# Output_block.net
KiCad netlist of a schematic drawn in Altium Designer
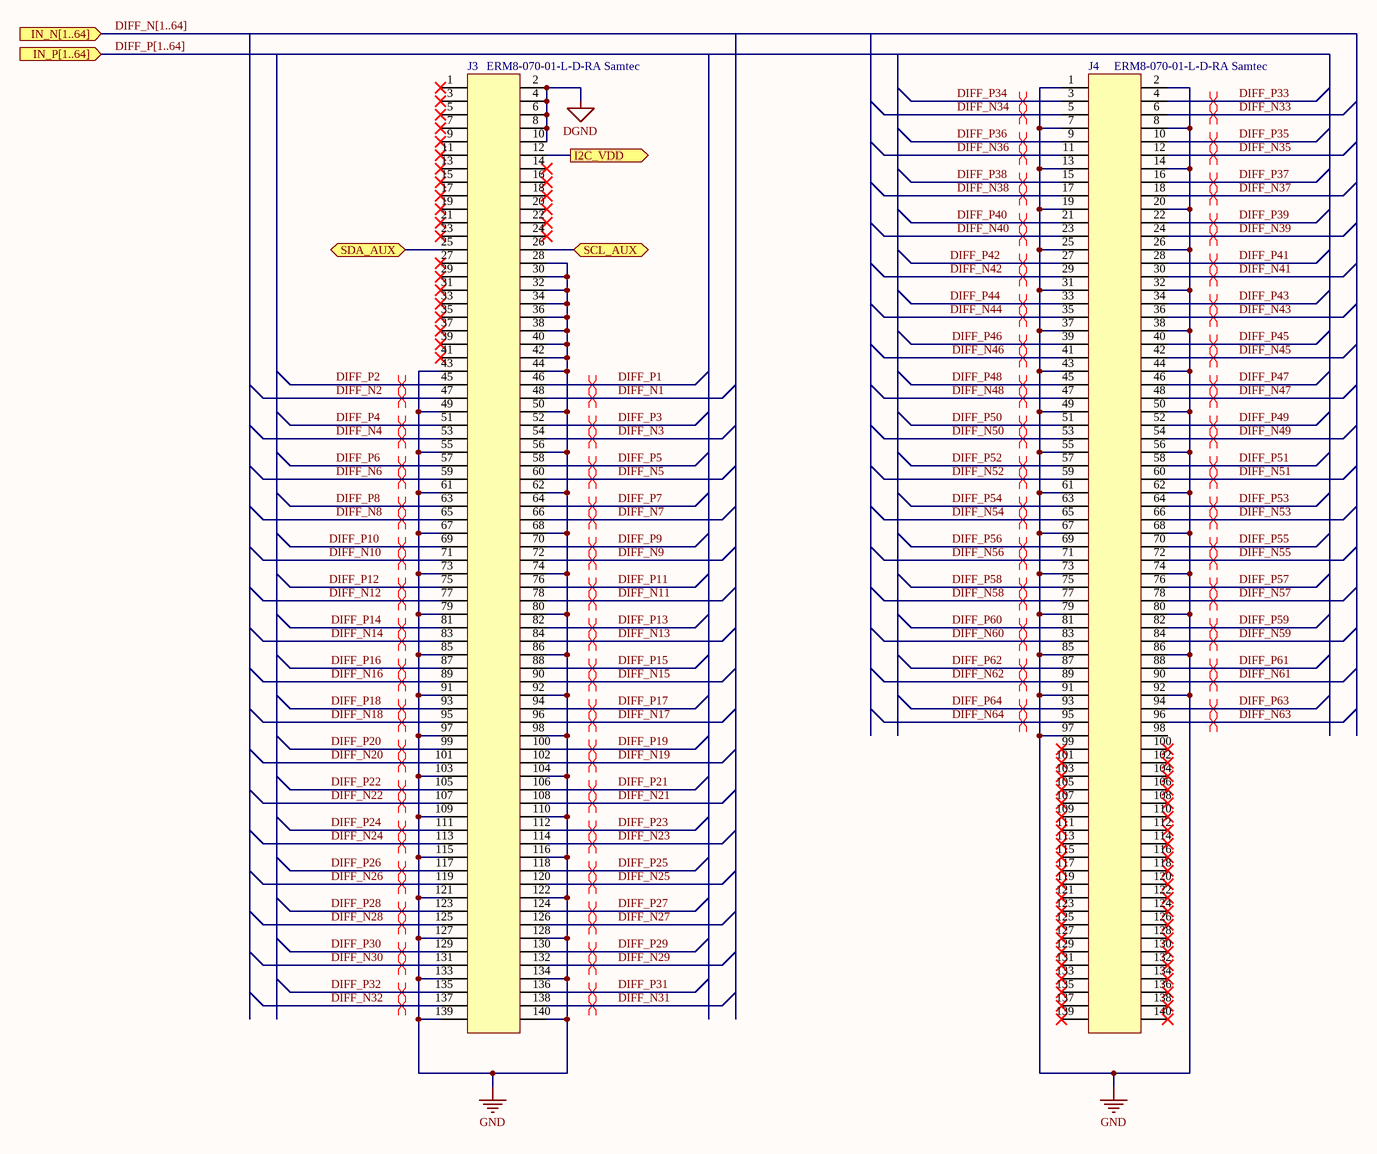
[diagram p0: Output_block.SchDoc]

(export (version "E")
  (design (tool "Eeschema 10.0.6"))
  (components
    (comp (ref "J3")
      (value "ERM8-070-01-L-D-RA Samtec")
      (footprint "ERM8-070-01-L-D-RA")
      (fields (field (name "MANUFACTURER") "Samtec"))
      (libsource (lib "Additional") (part "ERM8-070-01-L-D-RA"))
    )
    (comp (ref "J4")
      (value "ERM8-070-01-L-D-RA Samtec")
      (footprint "ERM8-070-01-L-D-RA")
      (fields (field (name "MANUFACTURER") "Samtec"))
      (libsource (lib "Additional") (part "ERM8-070-01-L-D-RA"))
    )
  )
  (nets
    (net (code "1") (name "/DIFF_N1") (class "Default") (node (ref "J3") (pin "48") (pintype "passive")))
    (net (code "2") (name "/DIFF_N2") (class "Default") (node (ref "J3") (pin "47") (pintype "passive")))
    (net (code "3") (name "/DIFF_N3") (class "Default") (node (ref "J3") (pin "54") (pintype "passive")))
    (net (code "4") (name "/DIFF_N4") (class "Default") (node (ref "J3") (pin "53") (pintype "passive")))
    (net (code "5") (name "/DIFF_N5") (class "Default") (node (ref "J3") (pin "60") (pintype "passive")))
    (net (code "6") (name "/DIFF_N6") (class "Default") (node (ref "J3") (pin "59") (pintype "passive")))
    (net (code "7") (name "/DIFF_N7") (class "Default") (node (ref "J3") (pin "66") (pintype "passive")))
    (net (code "8") (name "/DIFF_N8") (class "Default") (node (ref "J3") (pin "65") (pintype "passive")))
    (net (code "9") (name "/DIFF_N9") (class "Default") (node (ref "J3") (pin "72") (pintype "passive")))
    (net (code "10") (name "/DIFF_N10") (class "Default") (node (ref "J3") (pin "71") (pintype "passive")))
    (net (code "11") (name "/DIFF_N11") (class "Default") (node (ref "J3") (pin "78") (pintype "passive")))
    (net (code "12") (name "/DIFF_N12") (class "Default") (node (ref "J3") (pin "77") (pintype "passive")))
    (net (code "13") (name "/DIFF_N13") (class "Default") (node (ref "J3") (pin "84") (pintype "passive")))
    (net (code "14") (name "/DIFF_N14") (class "Default") (node (ref "J3") (pin "83") (pintype "passive")))
    (net (code "15") (name "/DIFF_N15") (class "Default") (node (ref "J3") (pin "90") (pintype "passive")))
    (net (code "16") (name "/DIFF_N16") (class "Default") (node (ref "J3") (pin "89") (pintype "passive")))
    (net (code "17") (name "/DIFF_N17") (class "Default") (node (ref "J3") (pin "96") (pintype "passive")))
    (net (code "18") (name "/DIFF_N18") (class "Default") (node (ref "J3") (pin "95") (pintype "passive")))
    (net (code "19") (name "/DIFF_N19") (class "Default") (node (ref "J3") (pin "102") (pintype "passive")))
    (net (code "20") (name "/DIFF_N20") (class "Default") (node (ref "J3") (pin "101") (pintype "passive")))
    (net (code "21") (name "/DIFF_N21") (class "Default") (node (ref "J3") (pin "108") (pintype "passive")))
    (net (code "22") (name "/DIFF_N22") (class "Default") (node (ref "J3") (pin "107") (pintype "passive")))
    (net (code "23") (name "/DIFF_N23") (class "Default") (node (ref "J3") (pin "114") (pintype "passive")))
    (net (code "24") (name "/DIFF_N24") (class "Default") (node (ref "J3") (pin "113") (pintype "passive")))
    (net (code "25") (name "/DIFF_N25") (class "Default") (node (ref "J3") (pin "120") (pintype "passive")))
    (net (code "26") (name "/DIFF_N26") (class "Default") (node (ref "J3") (pin "119") (pintype "passive")))
    (net (code "27") (name "/DIFF_N27") (class "Default") (node (ref "J3") (pin "126") (pintype "passive")))
    (net (code "28") (name "/DIFF_N28") (class "Default") (node (ref "J3") (pin "125") (pintype "passive")))
    (net (code "29") (name "/DIFF_N29") (class "Default") (node (ref "J3") (pin "132") (pintype "passive")))
    (net (code "30") (name "/DIFF_N30") (class "Default") (node (ref "J3") (pin "131") (pintype "passive")))
    (net (code "31") (name "/DIFF_N31") (class "Default") (node (ref "J3") (pin "138") (pintype "passive")))
    (net (code "32") (name "/DIFF_N32") (class "Default") (node (ref "J3") (pin "137") (pintype "passive")))
    (net (code "33") (name "/DIFF_N33") (class "Default") (node (ref "J4") (pin "6") (pintype "passive")))
    (net (code "34") (name "/DIFF_N34") (class "Default") (node (ref "J4") (pin "5") (pintype "passive")))
    (net (code "35") (name "/DIFF_N35") (class "Default") (node (ref "J4") (pin "12") (pintype "passive")))
    (net (code "36") (name "/DIFF_N36") (class "Default") (node (ref "J4") (pin "11") (pintype "passive")))
    (net (code "37") (name "/DIFF_N37") (class "Default") (node (ref "J4") (pin "18") (pintype "passive")))
    (net (code "38") (name "/DIFF_N38") (class "Default") (node (ref "J4") (pin "17") (pintype "passive")))
    (net (code "39") (name "/DIFF_N39") (class "Default") (node (ref "J4") (pin "24") (pintype "passive")))
    (net (code "40") (name "/DIFF_N40") (class "Default") (node (ref "J4") (pin "23") (pintype "passive")))
    (net (code "41") (name "/DIFF_N41") (class "Default") (node (ref "J4") (pin "30") (pintype "passive")))
    (net (code "42") (name "/DIFF_N42") (class "Default") (node (ref "J4") (pin "29") (pintype "passive")))
    (net (code "43") (name "/DIFF_N43") (class "Default") (node (ref "J4") (pin "36") (pintype "passive")))
    (net (code "44") (name "/DIFF_N44") (class "Default") (node (ref "J4") (pin "35") (pintype "passive")))
    (net (code "45") (name "/DIFF_N45") (class "Default") (node (ref "J4") (pin "42") (pintype "passive")))
    (net (code "46") (name "/DIFF_N46") (class "Default") (node (ref "J4") (pin "41") (pintype "passive")))
    (net (code "47") (name "/DIFF_N47") (class "Default") (node (ref "J4") (pin "48") (pintype "passive")))
    (net (code "48") (name "/DIFF_N48") (class "Default") (node (ref "J4") (pin "47") (pintype "passive")))
    (net (code "49") (name "/DIFF_N49") (class "Default") (node (ref "J4") (pin "54") (pintype "passive")))
    (net (code "50") (name "/DIFF_N50") (class "Default") (node (ref "J4") (pin "53") (pintype "passive")))
    (net (code "51") (name "/DIFF_N51") (class "Default") (node (ref "J4") (pin "60") (pintype "passive")))
    (net (code "52") (name "/DIFF_N52") (class "Default") (node (ref "J4") (pin "59") (pintype "passive")))
    (net (code "53") (name "/DIFF_N53") (class "Default") (node (ref "J4") (pin "66") (pintype "passive")))
    (net (code "54") (name "/DIFF_N54") (class "Default") (node (ref "J4") (pin "65") (pintype "passive")))
    (net (code "55") (name "/DIFF_N55") (class "Default") (node (ref "J4") (pin "72") (pintype "passive")))
    (net (code "56") (name "/DIFF_N56") (class "Default") (node (ref "J4") (pin "71") (pintype "passive")))
    (net (code "57") (name "/DIFF_N57") (class "Default") (node (ref "J4") (pin "78") (pintype "passive")))
    (net (code "58") (name "/DIFF_N58") (class "Default") (node (ref "J4") (pin "77") (pintype "passive")))
    (net (code "59") (name "/DIFF_N59") (class "Default") (node (ref "J4") (pin "84") (pintype "passive")))
    (net (code "60") (name "/DIFF_N60") (class "Default") (node (ref "J4") (pin "83") (pintype "passive")))
    (net (code "61") (name "/DIFF_N61") (class "Default") (node (ref "J4") (pin "90") (pintype "passive")))
    (net (code "62") (name "/DIFF_N62") (class "Default") (node (ref "J4") (pin "89") (pintype "passive")))
    (net (code "63") (name "/DIFF_N63") (class "Default") (node (ref "J4") (pin "96") (pintype "passive")))
    (net (code "64") (name "/DIFF_N64") (class "Default") (node (ref "J4") (pin "95") (pintype "passive")))
    (net (code "66") (name "/DIFF_P1") (class "Default") (node (ref "J3") (pin "46") (pintype "passive")))
    (net (code "67") (name "/DIFF_P2") (class "Default") (node (ref "J3") (pin "45") (pintype "passive")))
    (net (code "68") (name "/DIFF_P3") (class "Default") (node (ref "J3") (pin "52") (pintype "passive")))
    (net (code "69") (name "/DIFF_P4") (class "Default") (node (ref "J3") (pin "51") (pintype "passive")))
    (net (code "70") (name "/DIFF_P5") (class "Default") (node (ref "J3") (pin "58") (pintype "passive")))
    (net (code "71") (name "/DIFF_P6") (class "Default") (node (ref "J3") (pin "57") (pintype "passive")))
    (net (code "72") (name "/DIFF_P7") (class "Default") (node (ref "J3") (pin "64") (pintype "passive")))
    (net (code "73") (name "/DIFF_P8") (class "Default") (node (ref "J3") (pin "63") (pintype "passive")))
    (net (code "74") (name "/DIFF_P9") (class "Default") (node (ref "J3") (pin "70") (pintype "passive")))
    (net (code "75") (name "/DIFF_P10") (class "Default") (node (ref "J3") (pin "69") (pintype "passive")))
    (net (code "76") (name "/DIFF_P11") (class "Default") (node (ref "J3") (pin "76") (pintype "passive")))
    (net (code "77") (name "/DIFF_P12") (class "Default") (node (ref "J3") (pin "75") (pintype "passive")))
    (net (code "78") (name "/DIFF_P13") (class "Default") (node (ref "J3") (pin "82") (pintype "passive")))
    (net (code "79") (name "/DIFF_P14") (class "Default") (node (ref "J3") (pin "81") (pintype "passive")))
    (net (code "80") (name "/DIFF_P15") (class "Default") (node (ref "J3") (pin "88") (pintype "passive")))
    (net (code "81") (name "/DIFF_P16") (class "Default") (node (ref "J3") (pin "87") (pintype "passive")))
    (net (code "82") (name "/DIFF_P17") (class "Default") (node (ref "J3") (pin "94") (pintype "passive")))
    (net (code "83") (name "/DIFF_P18") (class "Default") (node (ref "J3") (pin "93") (pintype "passive")))
    (net (code "84") (name "/DIFF_P19") (class "Default") (node (ref "J3") (pin "100") (pintype "passive")))
    (net (code "85") (name "/DIFF_P20") (class "Default") (node (ref "J3") (pin "99") (pintype "passive")))
    (net (code "86") (name "/DIFF_P21") (class "Default") (node (ref "J3") (pin "106") (pintype "passive")))
    (net (code "87") (name "/DIFF_P22") (class "Default") (node (ref "J3") (pin "105") (pintype "passive")))
    (net (code "88") (name "/DIFF_P23") (class "Default") (node (ref "J3") (pin "112") (pintype "passive")))
    (net (code "89") (name "/DIFF_P24") (class "Default") (node (ref "J3") (pin "111") (pintype "passive")))
    (net (code "90") (name "/DIFF_P25") (class "Default") (node (ref "J3") (pin "118") (pintype "passive")))
    (net (code "91") (name "/DIFF_P26") (class "Default") (node (ref "J3") (pin "117") (pintype "passive")))
    (net (code "92") (name "/DIFF_P27") (class "Default") (node (ref "J3") (pin "124") (pintype "passive")))
    (net (code "93") (name "/DIFF_P28") (class "Default") (node (ref "J3") (pin "123") (pintype "passive")))
    (net (code "94") (name "/DIFF_P29") (class "Default") (node (ref "J3") (pin "130") (pintype "passive")))
    (net (code "95") (name "/DIFF_P30") (class "Default") (node (ref "J3") (pin "129") (pintype "passive")))
    (net (code "96") (name "/DIFF_P31") (class "Default") (node (ref "J3") (pin "136") (pintype "passive")))
    (net (code "97") (name "/DIFF_P32") (class "Default") (node (ref "J3") (pin "135") (pintype "passive")))
    (net (code "98") (name "/DIFF_P33") (class "Default") (node (ref "J4") (pin "4") (pintype "passive")))
    (net (code "99") (name "/DIFF_P34") (class "Default") (node (ref "J4") (pin "3") (pintype "passive")))
    (net (code "100") (name "/DIFF_P35") (class "Default") (node (ref "J4") (pin "10") (pintype "passive")))
    (net (code "101") (name "/DIFF_P36") (class "Default") (node (ref "J4") (pin "9") (pintype "passive")))
    (net (code "102") (name "/DIFF_P37") (class "Default") (node (ref "J4") (pin "16") (pintype "passive")))
    (net (code "103") (name "/DIFF_P38") (class "Default") (node (ref "J4") (pin "15") (pintype "passive")))
    (net (code "104") (name "/DIFF_P39") (class "Default") (node (ref "J4") (pin "22") (pintype "passive")))
    (net (code "105") (name "/DIFF_P40") (class "Default") (node (ref "J4") (pin "21") (pintype "passive")))
    (net (code "106") (name "/DIFF_P41") (class "Default") (node (ref "J4") (pin "28") (pintype "passive")))
    (net (code "107") (name "/DIFF_P42") (class "Default") (node (ref "J4") (pin "27") (pintype "passive")))
    (net (code "108") (name "/DIFF_P43") (class "Default") (node (ref "J4") (pin "34") (pintype "passive")))
    (net (code "109") (name "/DIFF_P44") (class "Default") (node (ref "J4") (pin "33") (pintype "passive")))
    (net (code "110") (name "/DIFF_P45") (class "Default") (node (ref "J4") (pin "40") (pintype "passive")))
    (net (code "111") (name "/DIFF_P46") (class "Default") (node (ref "J4") (pin "39") (pintype "passive")))
    (net (code "112") (name "/DIFF_P47") (class "Default") (node (ref "J4") (pin "46") (pintype "passive")))
    (net (code "113") (name "/DIFF_P48") (class "Default") (node (ref "J4") (pin "45") (pintype "passive")))
    (net (code "114") (name "/DIFF_P49") (class "Default") (node (ref "J4") (pin "52") (pintype "passive")))
    (net (code "115") (name "/DIFF_P50") (class "Default") (node (ref "J4") (pin "51") (pintype "passive")))
    (net (code "116") (name "/DIFF_P51") (class "Default") (node (ref "J4") (pin "58") (pintype "passive")))
    (net (code "117") (name "/DIFF_P52") (class "Default") (node (ref "J4") (pin "57") (pintype "passive")))
    (net (code "118") (name "/DIFF_P53") (class "Default") (node (ref "J4") (pin "64") (pintype "passive")))
    (net (code "119") (name "/DIFF_P54") (class "Default") (node (ref "J4") (pin "63") (pintype "passive")))
    (net (code "120") (name "/DIFF_P55") (class "Default") (node (ref "J4") (pin "70") (pintype "passive")))
    (net (code "121") (name "/DIFF_P56") (class "Default") (node (ref "J4") (pin "69") (pintype "passive")))
    (net (code "122") (name "/DIFF_P57") (class "Default") (node (ref "J4") (pin "76") (pintype "passive")))
    (net (code "123") (name "/DIFF_P58") (class "Default") (node (ref "J4") (pin "75") (pintype "passive")))
    (net (code "124") (name "/DIFF_P59") (class "Default") (node (ref "J4") (pin "82") (pintype "passive")))
    (net (code "125") (name "/DIFF_P60") (class "Default") (node (ref "J4") (pin "81") (pintype "passive")))
    (net (code "126") (name "/DIFF_P61") (class "Default") (node (ref "J4") (pin "88") (pintype "passive")))
    (net (code "127") (name "/DIFF_P62") (class "Default") (node (ref "J4") (pin "87") (pintype "passive")))
    (net (code "128") (name "/DIFF_P63") (class "Default") (node (ref "J4") (pin "94") (pintype "passive")))
    (net (code "129") (name "/DIFF_P64") (class "Default") (node (ref "J4") (pin "93") (pintype "passive")))
    (net (code "131") (name "/I2C_VDD") (class "Default") (node (ref "J3") (pin "12") (pintype "passive")))
    (net (code "132") (name "/SCL_AUX") (class "Default") (node (ref "J3") (pin "26") (pintype "passive")))
    (net (code "133") (name "/SDA_AUX") (class "Default") (node (ref "J3") (pin "25") (pintype "passive")))
    (net (code "134") (name "DGND") (class "Default")
      (node (ref "J3") (pin "10") (pintype "passive"))
      (node (ref "J3") (pin "2") (pintype "passive"))
      (node (ref "J3") (pin "4") (pintype "passive"))
      (node (ref "J3") (pin "6") (pintype "passive"))
      (node (ref "J3") (pin "8") (pintype "passive"))
    )
    (net (code "135") (name "GND") (class "Default")
      (node (ref "J3") (pin "103") (pintype "passive"))
      (node (ref "J3") (pin "104") (pintype "passive"))
      (node (ref "J3") (pin "109") (pintype "passive"))
      (node (ref "J3") (pin "110") (pintype "passive"))
      (node (ref "J3") (pin "115") (pintype "passive"))
      (node (ref "J3") (pin "116") (pintype "passive"))
      (node (ref "J3") (pin "121") (pintype "passive"))
      (node (ref "J3") (pin "122") (pintype "passive"))
      (node (ref "J3") (pin "127") (pintype "passive"))
      (node (ref "J3") (pin "128") (pintype "passive"))
      (node (ref "J3") (pin "133") (pintype "passive"))
      (node (ref "J3") (pin "134") (pintype "passive"))
      (node (ref "J3") (pin "139") (pintype "passive"))
      (node (ref "J3") (pin "140") (pintype "passive"))
      (node (ref "J3") (pin "28") (pintype "passive"))
      (node (ref "J3") (pin "30") (pintype "passive"))
      (node (ref "J3") (pin "32") (pintype "passive"))
      (node (ref "J3") (pin "34") (pintype "passive"))
      (node (ref "J3") (pin "36") (pintype "passive"))
      (node (ref "J3") (pin "38") (pintype "passive"))
      (node (ref "J3") (pin "40") (pintype "passive"))
      (node (ref "J3") (pin "42") (pintype "passive"))
      (node (ref "J3") (pin "43") (pintype "passive"))
      (node (ref "J3") (pin "44") (pintype "passive"))
      (node (ref "J3") (pin "49") (pintype "passive"))
      (node (ref "J3") (pin "50") (pintype "passive"))
      (node (ref "J3") (pin "55") (pintype "passive"))
      (node (ref "J3") (pin "56") (pintype "passive"))
      (node (ref "J3") (pin "61") (pintype "passive"))
      (node (ref "J3") (pin "62") (pintype "passive"))
      (node (ref "J3") (pin "67") (pintype "passive"))
      (node (ref "J3") (pin "68") (pintype "passive"))
      (node (ref "J3") (pin "73") (pintype "passive"))
      (node (ref "J3") (pin "74") (pintype "passive"))
      (node (ref "J3") (pin "79") (pintype "passive"))
      (node (ref "J3") (pin "80") (pintype "passive"))
      (node (ref "J3") (pin "85") (pintype "passive"))
      (node (ref "J3") (pin "86") (pintype "passive"))
      (node (ref "J3") (pin "91") (pintype "passive"))
      (node (ref "J3") (pin "92") (pintype "passive"))
      (node (ref "J3") (pin "97") (pintype "passive"))
      (node (ref "J3") (pin "98") (pintype "passive"))
      (node (ref "J4") (pin "1") (pintype "passive"))
      (node (ref "J4") (pin "13") (pintype "passive"))
      (node (ref "J4") (pin "14") (pintype "passive"))
      (node (ref "J4") (pin "19") (pintype "passive"))
      (node (ref "J4") (pin "2") (pintype "passive"))
      (node (ref "J4") (pin "20") (pintype "passive"))
      (node (ref "J4") (pin "25") (pintype "passive"))
      (node (ref "J4") (pin "26") (pintype "passive"))
      (node (ref "J4") (pin "31") (pintype "passive"))
      (node (ref "J4") (pin "32") (pintype "passive"))
      (node (ref "J4") (pin "37") (pintype "passive"))
      (node (ref "J4") (pin "38") (pintype "passive"))
      (node (ref "J4") (pin "43") (pintype "passive"))
      (node (ref "J4") (pin "44") (pintype "passive"))
      (node (ref "J4") (pin "49") (pintype "passive"))
      (node (ref "J4") (pin "50") (pintype "passive"))
      (node (ref "J4") (pin "55") (pintype "passive"))
      (node (ref "J4") (pin "56") (pintype "passive"))
      (node (ref "J4") (pin "61") (pintype "passive"))
      (node (ref "J4") (pin "62") (pintype "passive"))
      (node (ref "J4") (pin "67") (pintype "passive"))
      (node (ref "J4") (pin "68") (pintype "passive"))
      (node (ref "J4") (pin "7") (pintype "passive"))
      (node (ref "J4") (pin "73") (pintype "passive"))
      (node (ref "J4") (pin "74") (pintype "passive"))
      (node (ref "J4") (pin "79") (pintype "passive"))
      (node (ref "J4") (pin "8") (pintype "passive"))
      (node (ref "J4") (pin "80") (pintype "passive"))
      (node (ref "J4") (pin "85") (pintype "passive"))
      (node (ref "J4") (pin "86") (pintype "passive"))
      (node (ref "J4") (pin "91") (pintype "passive"))
      (node (ref "J4") (pin "92") (pintype "passive"))
      (node (ref "J4") (pin "97") (pintype "passive"))
    )
    (net (code "136") (name "unconnected-(J3-Pad1)") (class "Default")
      (node (ref "J3") (pin "1") (pintype "passive+no_connect"))
    )
    (net (code "137") (name "unconnected-(J3-Pad3)") (class "Default")
      (node (ref "J3") (pin "3") (pintype "passive+no_connect"))
    )
    (net (code "138") (name "unconnected-(J3-Pad5)") (class "Default")
      (node (ref "J3") (pin "5") (pintype "passive+no_connect"))
    )
    (net (code "139") (name "unconnected-(J3-Pad7)") (class "Default")
      (node (ref "J3") (pin "7") (pintype "passive+no_connect"))
    )
    (net (code "140") (name "unconnected-(J3-Pad9)") (class "Default")
      (node (ref "J3") (pin "9") (pintype "passive+no_connect"))
    )
    (net (code "141") (name "unconnected-(J3-Pad11)") (class "Default")
      (node (ref "J3") (pin "11") (pintype "passive+no_connect"))
    )
    (net (code "142") (name "unconnected-(J3-Pad13)") (class "Default")
      (node (ref "J3") (pin "13") (pintype "passive+no_connect"))
    )
    (net (code "143") (name "unconnected-(J3-Pad14)") (class "Default")
      (node (ref "J3") (pin "14") (pintype "passive+no_connect"))
    )
    (net (code "144") (name "unconnected-(J3-Pad15)") (class "Default")
      (node (ref "J3") (pin "15") (pintype "passive+no_connect"))
    )
    (net (code "145") (name "unconnected-(J3-Pad16)") (class "Default")
      (node (ref "J3") (pin "16") (pintype "passive+no_connect"))
    )
    (net (code "146") (name "unconnected-(J3-Pad17)") (class "Default")
      (node (ref "J3") (pin "17") (pintype "passive+no_connect"))
    )
    (net (code "147") (name "unconnected-(J3-Pad18)") (class "Default")
      (node (ref "J3") (pin "18") (pintype "passive+no_connect"))
    )
    (net (code "148") (name "unconnected-(J3-Pad19)") (class "Default")
      (node (ref "J3") (pin "19") (pintype "passive+no_connect"))
    )
    (net (code "149") (name "unconnected-(J3-Pad20)") (class "Default")
      (node (ref "J3") (pin "20") (pintype "passive+no_connect"))
    )
    (net (code "150") (name "unconnected-(J3-Pad21)") (class "Default")
      (node (ref "J3") (pin "21") (pintype "passive+no_connect"))
    )
    (net (code "151") (name "unconnected-(J3-Pad22)") (class "Default")
      (node (ref "J3") (pin "22") (pintype "passive+no_connect"))
    )
    (net (code "152") (name "unconnected-(J3-Pad23)") (class "Default")
      (node (ref "J3") (pin "23") (pintype "passive+no_connect"))
    )
    (net (code "153") (name "unconnected-(J3-Pad24)") (class "Default")
      (node (ref "J3") (pin "24") (pintype "passive+no_connect"))
    )
    (net (code "154") (name "unconnected-(J3-Pad27)") (class "Default")
      (node (ref "J3") (pin "27") (pintype "passive+no_connect"))
    )
    (net (code "155") (name "unconnected-(J3-Pad29)") (class "Default")
      (node (ref "J3") (pin "29") (pintype "passive+no_connect"))
    )
    (net (code "156") (name "unconnected-(J3-Pad31)") (class "Default")
      (node (ref "J3") (pin "31") (pintype "passive+no_connect"))
    )
    (net (code "157") (name "unconnected-(J3-Pad33)") (class "Default")
      (node (ref "J3") (pin "33") (pintype "passive+no_connect"))
    )
    (net (code "158") (name "unconnected-(J3-Pad35)") (class "Default")
      (node (ref "J3") (pin "35") (pintype "passive+no_connect"))
    )
    (net (code "159") (name "unconnected-(J3-Pad37)") (class "Default")
      (node (ref "J3") (pin "37") (pintype "passive+no_connect"))
    )
    (net (code "160") (name "unconnected-(J3-Pad39)") (class "Default")
      (node (ref "J3") (pin "39") (pintype "passive+no_connect"))
    )
    (net (code "161") (name "unconnected-(J3-Pad41)") (class "Default")
      (node (ref "J3") (pin "41") (pintype "passive+no_connect"))
    )
    (net (code "162") (name "unconnected-(J4-Pad98)") (class "Default")
      (node (ref "J4") (pin "98") (pintype "passive"))
    )
    (net (code "163") (name "unconnected-(J4-Pad99)") (class "Default")
      (node (ref "J4") (pin "99") (pintype "passive+no_connect"))
    )
    (net (code "164") (name "unconnected-(J4-Pad100)") (class "Default")
      (node (ref "J4") (pin "100") (pintype "passive+no_connect"))
    )
    (net (code "165") (name "unconnected-(J4-Pad101)") (class "Default")
      (node (ref "J4") (pin "101") (pintype "passive+no_connect"))
    )
    (net (code "166") (name "unconnected-(J4-Pad102)") (class "Default")
      (node (ref "J4") (pin "102") (pintype "passive+no_connect"))
    )
    (net (code "167") (name "unconnected-(J4-Pad103)") (class "Default")
      (node (ref "J4") (pin "103") (pintype "passive+no_connect"))
    )
    (net (code "168") (name "unconnected-(J4-Pad104)") (class "Default")
      (node (ref "J4") (pin "104") (pintype "passive+no_connect"))
    )
    (net (code "169") (name "unconnected-(J4-Pad105)") (class "Default")
      (node (ref "J4") (pin "105") (pintype "passive+no_connect"))
    )
    (net (code "170") (name "unconnected-(J4-Pad106)") (class "Default")
      (node (ref "J4") (pin "106") (pintype "passive+no_connect"))
    )
    (net (code "171") (name "unconnected-(J4-Pad107)") (class "Default")
      (node (ref "J4") (pin "107") (pintype "passive+no_connect"))
    )
    (net (code "172") (name "unconnected-(J4-Pad108)") (class "Default")
      (node (ref "J4") (pin "108") (pintype "passive+no_connect"))
    )
    (net (code "173") (name "unconnected-(J4-Pad109)") (class "Default")
      (node (ref "J4") (pin "109") (pintype "passive+no_connect"))
    )
    (net (code "174") (name "unconnected-(J4-Pad110)") (class "Default")
      (node (ref "J4") (pin "110") (pintype "passive+no_connect"))
    )
    (net (code "175") (name "unconnected-(J4-Pad111)") (class "Default")
      (node (ref "J4") (pin "111") (pintype "passive+no_connect"))
    )
    (net (code "176") (name "unconnected-(J4-Pad112)") (class "Default")
      (node (ref "J4") (pin "112") (pintype "passive+no_connect"))
    )
    (net (code "177") (name "unconnected-(J4-Pad113)") (class "Default")
      (node (ref "J4") (pin "113") (pintype "passive+no_connect"))
    )
    (net (code "178") (name "unconnected-(J4-Pad114)") (class "Default")
      (node (ref "J4") (pin "114") (pintype "passive+no_connect"))
    )
    (net (code "179") (name "unconnected-(J4-Pad115)") (class "Default")
      (node (ref "J4") (pin "115") (pintype "passive+no_connect"))
    )
    (net (code "180") (name "unconnected-(J4-Pad116)") (class "Default")
      (node (ref "J4") (pin "116") (pintype "passive+no_connect"))
    )
    (net (code "181") (name "unconnected-(J4-Pad117)") (class "Default")
      (node (ref "J4") (pin "117") (pintype "passive+no_connect"))
    )
    (net (code "182") (name "unconnected-(J4-Pad118)") (class "Default")
      (node (ref "J4") (pin "118") (pintype "passive+no_connect"))
    )
    (net (code "183") (name "unconnected-(J4-Pad119)") (class "Default")
      (node (ref "J4") (pin "119") (pintype "passive+no_connect"))
    )
    (net (code "184") (name "unconnected-(J4-Pad120)") (class "Default")
      (node (ref "J4") (pin "120") (pintype "passive+no_connect"))
    )
    (net (code "185") (name "unconnected-(J4-Pad121)") (class "Default")
      (node (ref "J4") (pin "121") (pintype "passive+no_connect"))
    )
    (net (code "186") (name "unconnected-(J4-Pad122)") (class "Default")
      (node (ref "J4") (pin "122") (pintype "passive+no_connect"))
    )
    (net (code "187") (name "unconnected-(J4-Pad123)") (class "Default")
      (node (ref "J4") (pin "123") (pintype "passive+no_connect"))
    )
    (net (code "188") (name "unconnected-(J4-Pad124)") (class "Default")
      (node (ref "J4") (pin "124") (pintype "passive+no_connect"))
    )
    (net (code "189") (name "unconnected-(J4-Pad125)") (class "Default")
      (node (ref "J4") (pin "125") (pintype "passive+no_connect"))
    )
    (net (code "190") (name "unconnected-(J4-Pad126)") (class "Default")
      (node (ref "J4") (pin "126") (pintype "passive+no_connect"))
    )
    (net (code "191") (name "unconnected-(J4-Pad127)") (class "Default")
      (node (ref "J4") (pin "127") (pintype "passive+no_connect"))
    )
    (net (code "192") (name "unconnected-(J4-Pad128)") (class "Default")
      (node (ref "J4") (pin "128") (pintype "passive+no_connect"))
    )
    (net (code "193") (name "unconnected-(J4-Pad129)") (class "Default")
      (node (ref "J4") (pin "129") (pintype "passive+no_connect"))
    )
    (net (code "194") (name "unconnected-(J4-Pad130)") (class "Default")
      (node (ref "J4") (pin "130") (pintype "passive+no_connect"))
    )
    (net (code "195") (name "unconnected-(J4-Pad131)") (class "Default")
      (node (ref "J4") (pin "131") (pintype "passive+no_connect"))
    )
    (net (code "196") (name "unconnected-(J4-Pad132)") (class "Default")
      (node (ref "J4") (pin "132") (pintype "passive+no_connect"))
    )
    (net (code "197") (name "unconnected-(J4-Pad133)") (class "Default")
      (node (ref "J4") (pin "133") (pintype "passive+no_connect"))
    )
    (net (code "198") (name "unconnected-(J4-Pad134)") (class "Default")
      (node (ref "J4") (pin "134") (pintype "passive+no_connect"))
    )
    (net (code "199") (name "unconnected-(J4-Pad135)") (class "Default")
      (node (ref "J4") (pin "135") (pintype "passive+no_connect"))
    )
    (net (code "200") (name "unconnected-(J4-Pad136)") (class "Default")
      (node (ref "J4") (pin "136") (pintype "passive+no_connect"))
    )
    (net (code "201") (name "unconnected-(J4-Pad137)") (class "Default")
      (node (ref "J4") (pin "137") (pintype "passive+no_connect"))
    )
    (net (code "202") (name "unconnected-(J4-Pad138)") (class "Default")
      (node (ref "J4") (pin "138") (pintype "passive+no_connect"))
    )
    (net (code "203") (name "unconnected-(J4-Pad139)") (class "Default")
      (node (ref "J4") (pin "139") (pintype "passive+no_connect"))
    )
    (net (code "204") (name "unconnected-(J4-Pad140)") (class "Default")
      (node (ref "J4") (pin "140") (pintype "passive+no_connect"))
    )
  )
)
